# esquema_v1.net
KiCad netlist of a schematic drawn in EAGLE
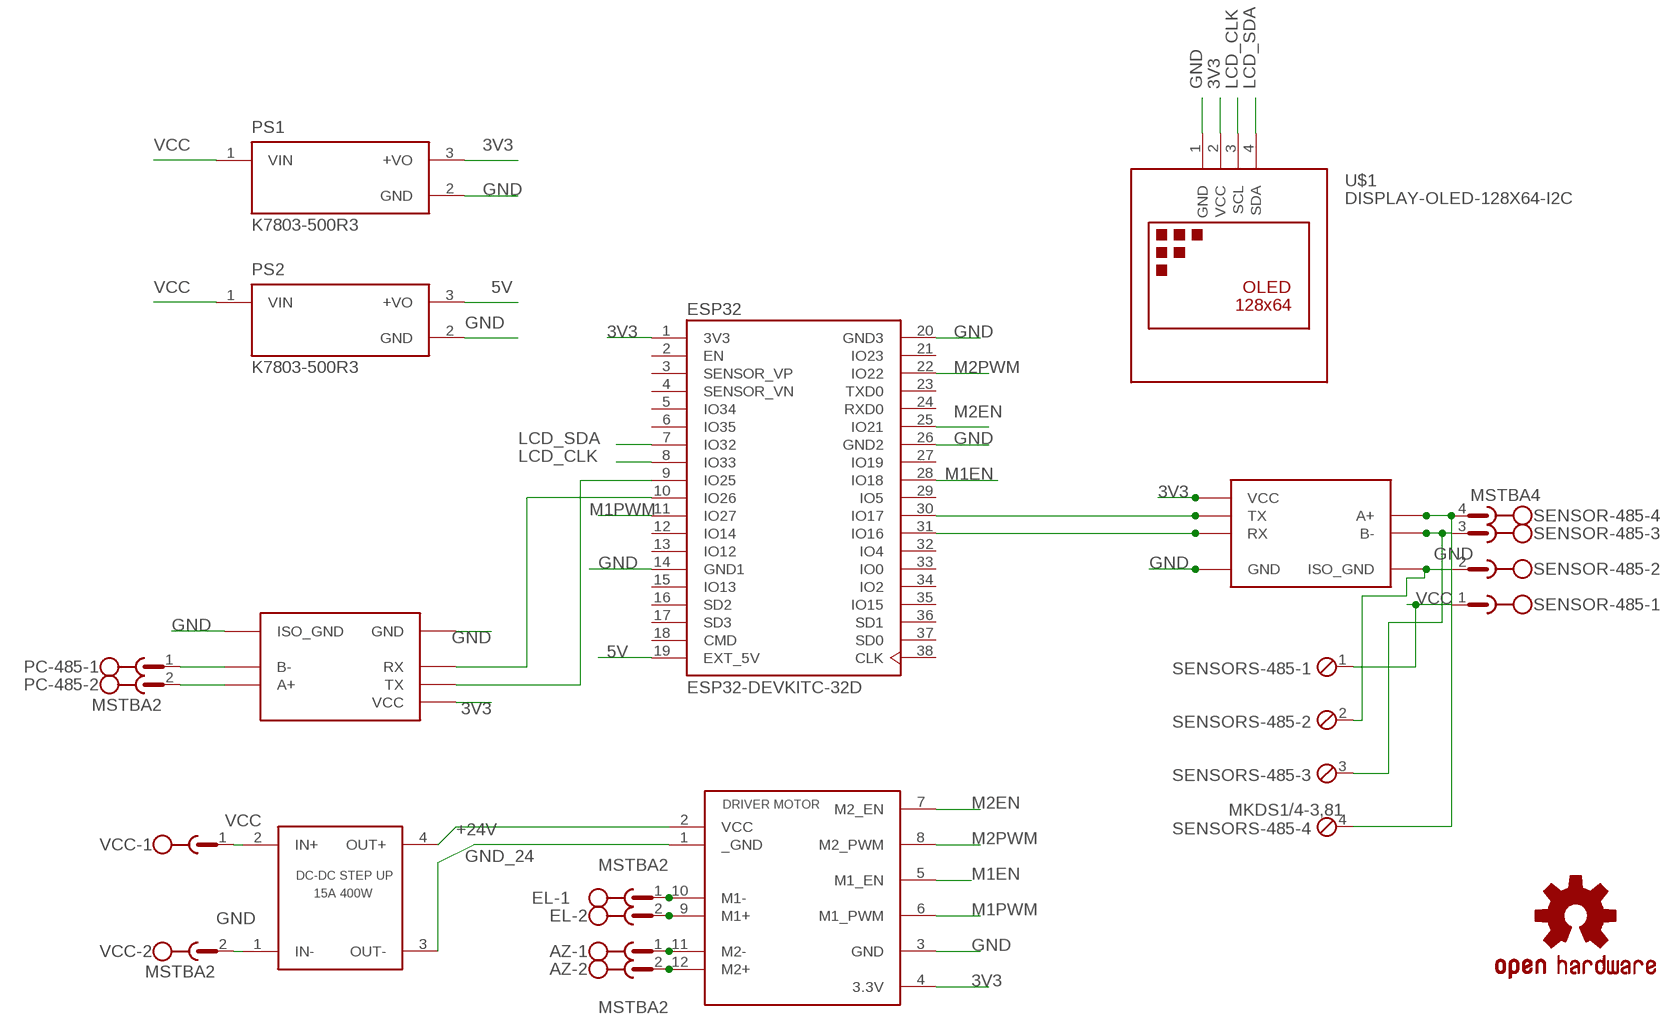
[diagram p0: schematic, sheet 1]

(export (version "E")
  (design (tool "Eeschema 10.0.6"))
  (components
    (comp (ref "AZ")
      (value "MSTBA2")
      (footprint "eagle-import:MSTBA2")
      (fields (field (name "MF") "FARNELL") (field (name "MPN") "1757242"))
      (libsource (lib "eagle-import") (part "MSTBA2"))
    )
    (comp (ref "EL")
      (value "MSTBA2")
      (footprint "eagle-import:MSTBA2")
      (fields (field (name "MF") "FARNELL") (field (name "MPN") "1757242"))
      (libsource (lib "eagle-import") (part "MSTBA2"))
    )
    (comp (ref "ESP32")
      (value "ESP32-DEVKITC-32D")
      (footprint "eagle-import:MODULE_ESP32-DEVKITC-32D")
      (fields (field (name "MF") "Espressif Systems"))
      (libsource (lib "eagle-import") (part "ESP32-DEVKITC-32D"))
    )
    (comp (ref "LOGO1")
      (value "OSHW-LOGOMINI")
      (footprint "eagle-import:OSHW-LOGO-MINI")
      (libsource (lib "eagle-import") (part "OSHW-LOGOMINI"))
    )
    (comp (ref "M1")
      (value "DRIVER_MOTOR")
      (footprint "eagle-import:DRIVER_MOTOR")
      (libsource (lib "eagle-import") (part "DRIVER_MOTOR"))
    )
    (comp (ref "M2")
      (value "DC-DC_STRP_UP")
      (footprint "eagle-import:DC-DC-SETP-UP")
      (libsource (lib "eagle-import") (part "DC-DC_STRP_UP"))
    )
    (comp (ref "M3")
      (value "LIMNOTECH_SMC_RS485")
      (footprint "eagle-import:LIMNOTECH_SMC_RS485")
      (libsource (lib "eagle-import") (part "LIMNOTECH_SMC_RS485"))
    )
    (comp (ref "M4")
      (value "LIMNOTECH_SMC_RS485")
      (footprint "eagle-import:LIMNOTECH_SMC_RS485")
      (libsource (lib "eagle-import") (part "LIMNOTECH_SMC_RS485"))
    )
    (comp (ref "PC-485")
      (value "MSTBA2")
      (footprint "eagle-import:MSTBA2")
      (fields (field (name "MF") "FARNELL") (field (name "MPN") "1757242"))
      (libsource (lib "eagle-import") (part "MSTBA2"))
    )
    (comp (ref "PS1")
      (value "K7803-500R3")
      (footprint "eagle-import:CONV_K7803-500R3")
      (fields (field (name "MF") "Mornsun America, LLC"))
      (libsource (lib "eagle-import") (part "K7803-500R3"))
    )
    (comp (ref "PS2")
      (value "K7803-500R3")
      (footprint "eagle-import:CONV_K7803-500R3")
      (fields (field (name "MF") "Mornsun America, LLC"))
      (libsource (lib "eagle-import") (part "K7803-500R3"))
    )
    (comp (ref "SENSOR-485")
      (value "MSTBA4")
      (footprint "eagle-import:MSTBA4")
      (fields (field (name "MF") "FARNELL") (field (name "MPN") "1757268"))
      (libsource (lib "eagle-import") (part "MSTBA4"))
    )
    (comp (ref "SENSORS-485")
      (value "MKDS1/4-3,81")
      (footprint "eagle-import:4POL381")
      (libsource (lib "eagle-import") (part "MKDS1/4-3,81"))
    )
    (comp (ref "U$1")
      (value "DISPLAY-OLED-128X64-I2C")
      (footprint "eagle-import:DISPLAY-OLED-128X64-I2C")
      (libsource (lib "eagle-import") (part "DISPLAY-OLED-128X64-I2C"))
    )
    (comp (ref "VCC")
      (value "MSTBA2")
      (footprint "eagle-import:MSTBA2")
      (fields (field (name "MF") "FARNELL") (field (name "MPN") "1757242"))
      (libsource (lib "eagle-import") (part "MSTBA2"))
    )
  )
  (nets
    (net (code "1") (name "/+24V") (class "Default")
      (node (ref "M1") (pin "2") (pinfunction "VCC_2") (pintype "bidirectional"))
      (node (ref "M2") (pin "4") (pinfunction "OUT+_4") (pintype "bidirectional"))
    )
    (net (code "2") (name "/3V3") (class "Default")
      (node (ref "ESP32") (pin "1") (pinfunction "3V3_1") (pintype "power_in"))
      (node (ref "M1") (pin "4") (pinfunction "3.3V_4") (pintype "bidirectional"))
      (node (ref "M3") (pin "VCC") (pinfunction "VCC_VCC") (pintype "bidirectional"))
      (node (ref "M4") (pin "VCC") (pinfunction "VCC_VCC") (pintype "bidirectional"))
      (node (ref "PS1") (pin "3") (pinfunction "+VO_3") (pintype "output"))
      (node (ref "U$1") (pin "2") (pinfunction "VCC_2") (pintype "power_in"))
    )
    (net (code "3") (name "/5V") (class "Default")
      (node (ref "ESP32") (pin "19") (pinfunction "EXT_5V_19") (pintype "power_in"))
      (node (ref "PS2") (pin "3") (pinfunction "+VO_3") (pintype "output"))
    )
    (net (code "4") (name "/GND") (class "Default")
      (node (ref "ESP32") (pin "14") (pinfunction "GND1_14") (pintype "power_in"))
      (node (ref "ESP32") (pin "20") (pinfunction "GND3_20") (pintype "power_in"))
      (node (ref "ESP32") (pin "26") (pinfunction "GND2_26") (pintype "power_in"))
      (node (ref "M1") (pin "3") (pinfunction "GND_3") (pintype "bidirectional"))
      (node (ref "M2") (pin "1") (pinfunction "IN-_1") (pintype "bidirectional"))
      (node (ref "M3") (pin "GND") (pinfunction "GND_GND") (pintype "bidirectional"))
      (node (ref "M3") (pin "GND_ISO") (pinfunction "ISO_GND_GND_ISO") (pintype "bidirectional"))
      (node (ref "M4") (pin "GND") (pinfunction "GND_GND") (pintype "bidirectional"))
      (node (ref "M4") (pin "GND_ISO") (pinfunction "ISO_GND_GND_ISO") (pintype "bidirectional"))
      (node (ref "PS1") (pin "2") (pinfunction "GND_2") (pintype "power_in"))
      (node (ref "PS2") (pin "2") (pinfunction "GND_2") (pintype "power_in"))
      (node (ref "SENSOR-485") (pin "2") (pinfunction "1_2") (pintype "passive"))
      (node (ref "SENSORS-485") (pin "2") (pinfunction "1_2") (pintype "passive"))
      (node (ref "U$1") (pin "1") (pinfunction "GND_1") (pintype "power_in"))
      (node (ref "VCC") (pin "2") (pinfunction "1_2") (pintype "passive"))
    )
    (net (code "5") (name "/GND_24") (class "Default")
      (node (ref "M1") (pin "1") (pinfunction "_GND_1") (pintype "bidirectional"))
      (node (ref "M2") (pin "3") (pinfunction "OUT-_3") (pintype "bidirectional"))
    )
    (net (code "6") (name "/LCD_CLK") (class "Default")
      (node (ref "ESP32") (pin "8") (pinfunction "IO33_8") (pintype "bidirectional"))
      (node (ref "U$1") (pin "3") (pinfunction "SCL_3") (pintype "bidirectional"))
    )
    (net (code "7") (name "/LCD_SDA") (class "Default")
      (node (ref "ESP32") (pin "7") (pinfunction "IO32_7") (pintype "bidirectional"))
      (node (ref "U$1") (pin "4") (pinfunction "SDA_4") (pintype "bidirectional"))
    )
    (net (code "8") (name "/M1EN") (class "Default")
      (node (ref "ESP32") (pin "28") (pinfunction "IO18_28") (pintype "bidirectional"))
      (node (ref "M1") (pin "5") (pinfunction "M1_EN_5") (pintype "bidirectional"))
    )
    (net (code "9") (name "/M1PWM") (class "Default")
      (node (ref "ESP32") (pin "11") (pinfunction "IO27_11") (pintype "bidirectional"))
      (node (ref "M1") (pin "6") (pinfunction "M1_PWM_6") (pintype "bidirectional"))
    )
    (net (code "10") (name "/M2EN") (class "Default")
      (node (ref "ESP32") (pin "25") (pinfunction "IO21_25") (pintype "bidirectional"))
      (node (ref "M1") (pin "7") (pinfunction "M2_EN_7") (pintype "bidirectional"))
    )
    (net (code "11") (name "/M2PWM") (class "Default")
      (node (ref "ESP32") (pin "22") (pinfunction "IO22_22") (pintype "bidirectional"))
      (node (ref "M1") (pin "8") (pinfunction "M2_PWM_8") (pintype "bidirectional"))
    )
    (net (code "12") (name "/VCC") (class "Default")
      (node (ref "M2") (pin "2") (pinfunction "IN+_2") (pintype "bidirectional"))
      (node (ref "PS1") (pin "1") (pinfunction "VIN_1") (pintype "input"))
      (node (ref "PS2") (pin "1") (pinfunction "VIN_1") (pintype "input"))
      (node (ref "SENSOR-485") (pin "1") (pinfunction "1_1") (pintype "passive"))
      (node (ref "SENSORS-485") (pin "1") (pinfunction "1_1") (pintype "passive"))
      (node (ref "VCC") (pin "1") (pinfunction "1_1") (pintype "passive"))
    )
    (net (code "13") (name "Net-(AZB-1)") (class "Default")
      (node (ref "AZ") (pin "2") (pinfunction "1_2") (pintype "passive"))
      (node (ref "M1") (pin "12") (pinfunction "M2+_12") (pintype "bidirectional"))
    )
    (net (code "14") (name "Net-(ELB-1)") (class "Default")
      (node (ref "EL") (pin "2") (pinfunction "1_2") (pintype "passive"))
      (node (ref "M1") (pin "9") (pinfunction "M1+_9") (pintype "bidirectional"))
    )
    (net (code "15") (name "Net-(ESP32-IO16)") (class "Default")
      (node (ref "ESP32") (pin "31") (pinfunction "IO16_31") (pintype "bidirectional"))
      (node (ref "M4") (pin "RX") (pinfunction "RX_RX") (pintype "bidirectional"))
    )
    (net (code "16") (name "Net-(ESP32-IO17)") (class "Default")
      (node (ref "ESP32") (pin "30") (pinfunction "IO17_30") (pintype "bidirectional"))
      (node (ref "M4") (pin "TX") (pinfunction "TX_TX") (pintype "bidirectional"))
    )
    (net (code "17") (name "Net-(ESP32-IO25)") (class "Default")
      (node (ref "ESP32") (pin "9") (pinfunction "IO25_9") (pintype "bidirectional"))
      (node (ref "M3") (pin "TX") (pinfunction "TX_TX") (pintype "bidirectional"))
    )
    (net (code "18") (name "Net-(ESP32-IO26)") (class "Default")
      (node (ref "ESP32") (pin "10") (pinfunction "IO26_10") (pintype "bidirectional"))
      (node (ref "M3") (pin "RX") (pinfunction "RX_RX") (pintype "bidirectional"))
    )
    (net (code "19") (name "Net-(M1-M1-)") (class "Default")
      (node (ref "EL") (pin "1") (pinfunction "1_1") (pintype "passive"))
      (node (ref "M1") (pin "10") (pinfunction "M1-_10") (pintype "bidirectional"))
    )
    (net (code "20") (name "Net-(M1-M2-)") (class "Default")
      (node (ref "AZ") (pin "1") (pinfunction "1_1") (pintype "passive"))
      (node (ref "M1") (pin "11") (pinfunction "M2-_11") (pintype "bidirectional"))
    )
    (net (code "21") (name "Net-(M3-PadB-)") (class "Default")
      (node (ref "M3") (pin "B-") (pinfunction "B-_B-") (pintype "bidirectional"))
      (node (ref "PC-485") (pin "1") (pinfunction "1_1") (pintype "passive"))
    )
    (net (code "22") (name "Net-(PC-485B-1)") (class "Default")
      (node (ref "M3") (pin "A+") (pinfunction "A+_A+") (pintype "bidirectional"))
      (node (ref "PC-485") (pin "2") (pinfunction "1_2") (pintype "passive"))
    )
    (net (code "23") (name "Net-(SENSOR-485C-1)") (class "Default")
      (node (ref "M4") (pin "B-") (pinfunction "B-_B-") (pintype "bidirectional"))
      (node (ref "SENSOR-485") (pin "3") (pinfunction "1_3") (pintype "passive"))
      (node (ref "SENSORS-485") (pin "3") (pinfunction "1_3") (pintype "passive"))
    )
    (net (code "24") (name "Net-(SENSOR-485D-1)") (class "Default")
      (node (ref "M4") (pin "A+") (pinfunction "A+_A+") (pintype "bidirectional"))
      (node (ref "SENSOR-485") (pin "4") (pinfunction "1_4") (pintype "passive"))
      (node (ref "SENSORS-485") (pin "4") (pinfunction "1_4") (pintype "passive"))
    )
    (net (code "25") (name "unconnected-(ESP32-CLK-Pad38)") (class "Default")
      (node (ref "ESP32") (pin "38") (pinfunction "CLK_38") (pintype "input"))
    )
    (net (code "26") (name "unconnected-(ESP32-CMD-Pad18)") (class "Default")
      (node (ref "ESP32") (pin "18") (pinfunction "CMD_18") (pintype "bidirectional"))
    )
    (net (code "27") (name "unconnected-(ESP32-EN-Pad2)") (class "Default")
      (node (ref "ESP32") (pin "2") (pinfunction "EN_2") (pintype "input"))
    )
    (net (code "28") (name "unconnected-(ESP32-IO0-Pad33)") (class "Default")
      (node (ref "ESP32") (pin "33") (pinfunction "IO0_33") (pintype "bidirectional"))
    )
    (net (code "29") (name "unconnected-(ESP32-IO2-Pad34)") (class "Default")
      (node (ref "ESP32") (pin "34") (pinfunction "IO2_34") (pintype "bidirectional"))
    )
    (net (code "30") (name "unconnected-(ESP32-IO4-Pad32)") (class "Default")
      (node (ref "ESP32") (pin "32") (pinfunction "IO4_32") (pintype "bidirectional"))
    )
    (net (code "31") (name "unconnected-(ESP32-IO5-Pad29)") (class "Default")
      (node (ref "ESP32") (pin "29") (pinfunction "IO5_29") (pintype "bidirectional"))
    )
    (net (code "32") (name "unconnected-(ESP32-IO12-Pad13)") (class "Default")
      (node (ref "ESP32") (pin "13") (pinfunction "IO12_13") (pintype "bidirectional"))
    )
    (net (code "33") (name "unconnected-(ESP32-IO13-Pad15)") (class "Default")
      (node (ref "ESP32") (pin "15") (pinfunction "IO13_15") (pintype "bidirectional"))
    )
    (net (code "34") (name "unconnected-(ESP32-IO14-Pad12)") (class "Default")
      (node (ref "ESP32") (pin "12") (pinfunction "IO14_12") (pintype "bidirectional"))
    )
    (net (code "35") (name "unconnected-(ESP32-IO15-Pad35)") (class "Default")
      (node (ref "ESP32") (pin "35") (pinfunction "IO15_35") (pintype "bidirectional"))
    )
    (net (code "36") (name "unconnected-(ESP32-IO19-Pad27)") (class "Default")
      (node (ref "ESP32") (pin "27") (pinfunction "IO19_27") (pintype "bidirectional"))
    )
    (net (code "37") (name "unconnected-(ESP32-IO23-Pad21)") (class "Default")
      (node (ref "ESP32") (pin "21") (pinfunction "IO23_21") (pintype "bidirectional"))
    )
    (net (code "38") (name "unconnected-(ESP32-IO34-Pad5)") (class "Default")
      (node (ref "ESP32") (pin "5") (pinfunction "IO34_5") (pintype "bidirectional"))
    )
    (net (code "39") (name "unconnected-(ESP32-IO35-Pad6)") (class "Default")
      (node (ref "ESP32") (pin "6") (pinfunction "IO35_6") (pintype "bidirectional"))
    )
    (net (code "40") (name "unconnected-(ESP32-RXD0-Pad24)") (class "Default")
      (node (ref "ESP32") (pin "24") (pinfunction "RXD0_24") (pintype "input"))
    )
    (net (code "41") (name "unconnected-(ESP32-SD0-Pad37)") (class "Default")
      (node (ref "ESP32") (pin "37") (pinfunction "SD0_37") (pintype "bidirectional"))
    )
    (net (code "42") (name "unconnected-(ESP32-SD1-Pad36)") (class "Default")
      (node (ref "ESP32") (pin "36") (pinfunction "SD1_36") (pintype "bidirectional"))
    )
    (net (code "43") (name "unconnected-(ESP32-SD2-Pad16)") (class "Default")
      (node (ref "ESP32") (pin "16") (pinfunction "SD2_16") (pintype "bidirectional"))
    )
    (net (code "44") (name "unconnected-(ESP32-SD3-Pad17)") (class "Default")
      (node (ref "ESP32") (pin "17") (pinfunction "SD3_17") (pintype "bidirectional"))
    )
    (net (code "45") (name "unconnected-(ESP32-SENSOR_VN-Pad4)") (class "Default")
      (node (ref "ESP32") (pin "4") (pinfunction "SENSOR_VN_4") (pintype "input"))
    )
    (net (code "46") (name "unconnected-(ESP32-SENSOR_VP-Pad3)") (class "Default")
      (node (ref "ESP32") (pin "3") (pinfunction "SENSOR_VP_3") (pintype "input"))
    )
    (net (code "47") (name "unconnected-(ESP32-TXD0-Pad23)") (class "Default")
      (node (ref "ESP32") (pin "23") (pinfunction "TXD0_23") (pintype "output"))
    )
  )
)
